# Test_Pack.net
KiCad netlist of a schematic drawn in EAGLE
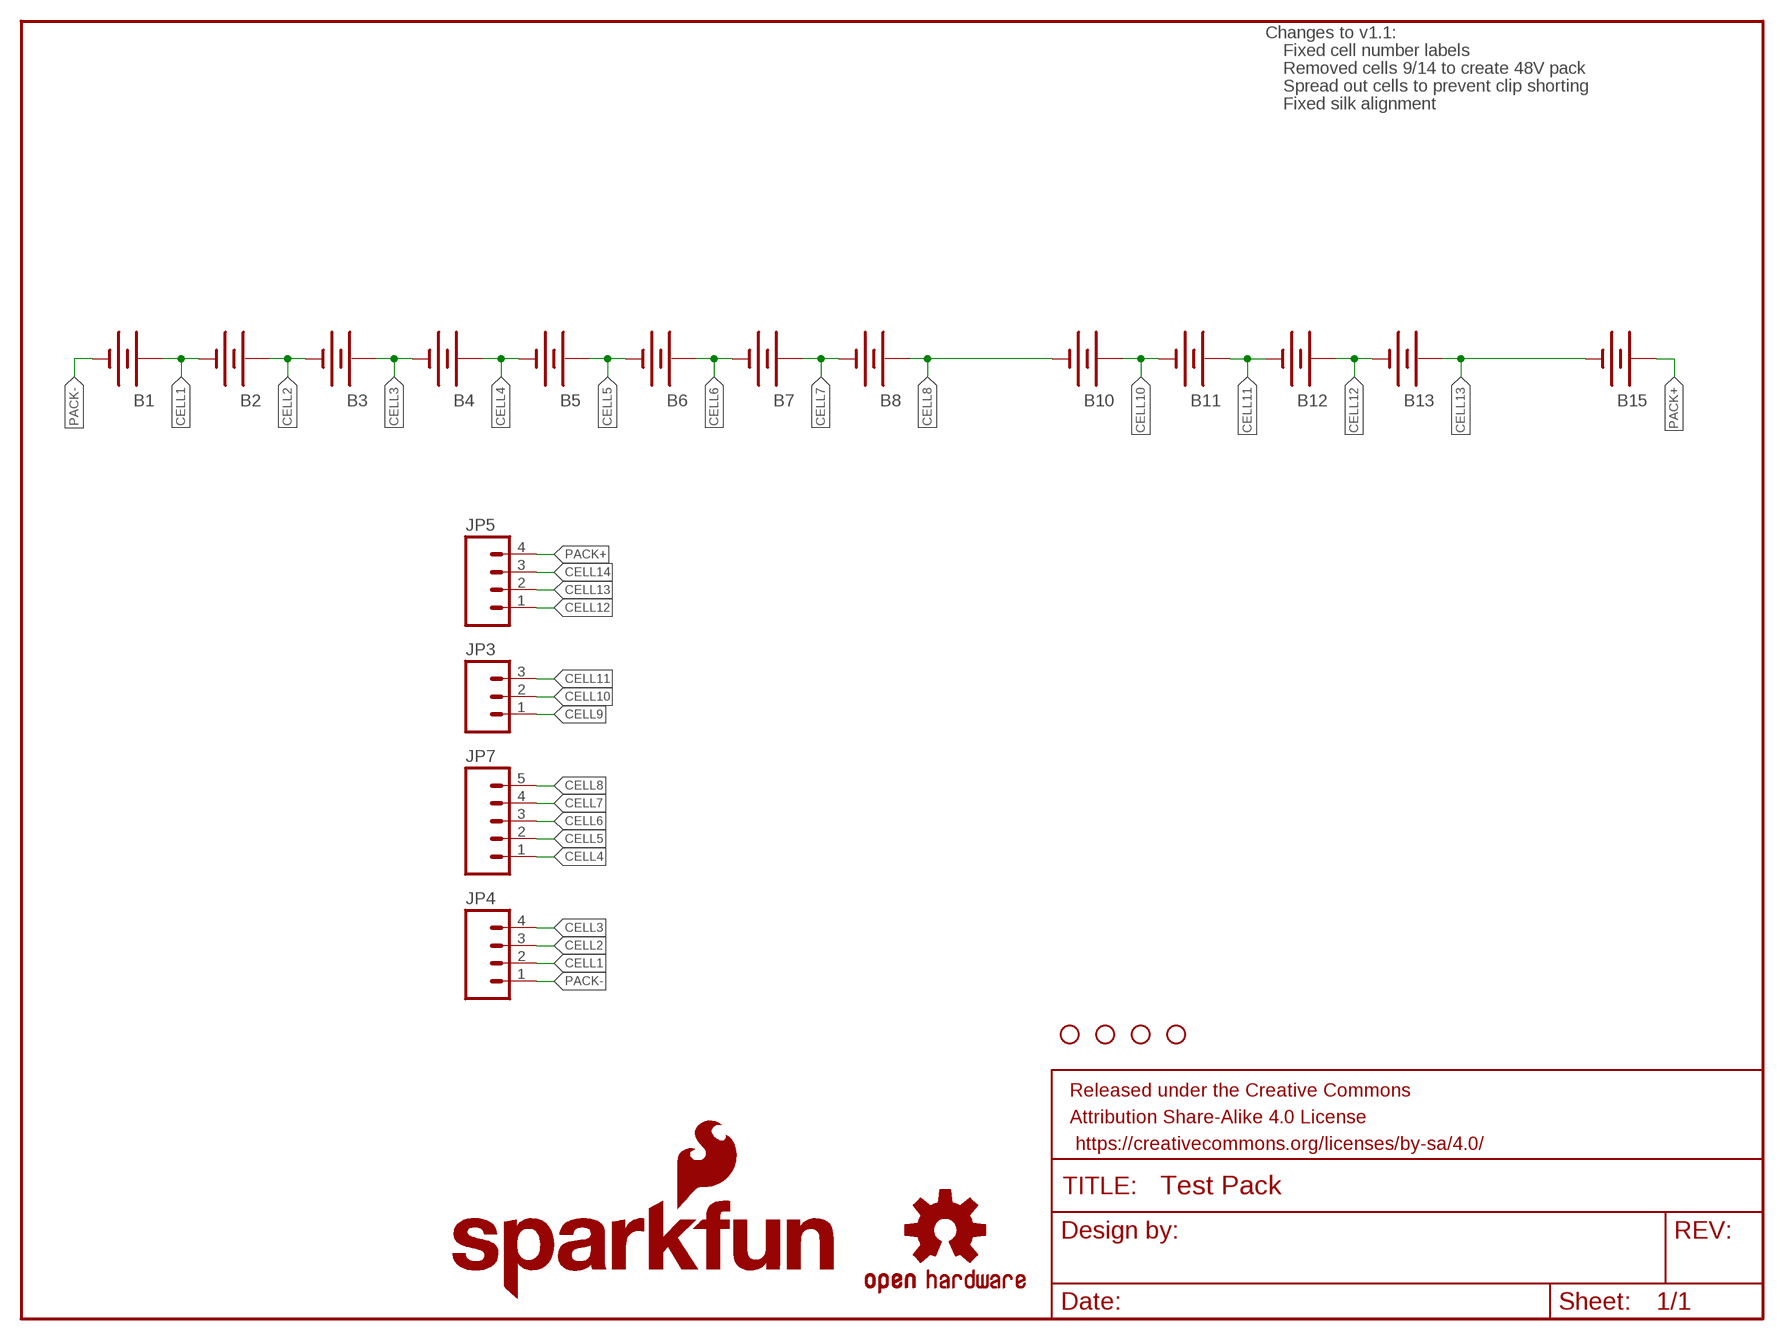
[diagram p0: schematic, sheet 1]

(export (version "E")
  (design (tool "Eeschema 10.0.6"))
  (components
    (comp (ref "B1")
      (value "BATTERY18650")
      (footprint "eagle-import:BATTERY_18650-HOLDER")
      (libsource (lib "eagle-import") (part "BATTERY18650"))
    )
    (comp (ref "B2")
      (value "BATTERY18650")
      (footprint "eagle-import:BATTERY_18650-HOLDER")
      (libsource (lib "eagle-import") (part "BATTERY18650"))
    )
    (comp (ref "B3")
      (value "BATTERY18650")
      (footprint "eagle-import:BATTERY_18650-HOLDER")
      (libsource (lib "eagle-import") (part "BATTERY18650"))
    )
    (comp (ref "B4")
      (value "BATTERY18650")
      (footprint "eagle-import:BATTERY_18650-HOLDER")
      (libsource (lib "eagle-import") (part "BATTERY18650"))
    )
    (comp (ref "B5")
      (value "BATTERY18650")
      (footprint "eagle-import:BATTERY_18650-HOLDER")
      (libsource (lib "eagle-import") (part "BATTERY18650"))
    )
    (comp (ref "B6")
      (value "BATTERY18650")
      (footprint "eagle-import:BATTERY_18650-HOLDER")
      (libsource (lib "eagle-import") (part "BATTERY18650"))
    )
    (comp (ref "B7")
      (value "BATTERY18650")
      (footprint "eagle-import:BATTERY_18650-HOLDER")
      (libsource (lib "eagle-import") (part "BATTERY18650"))
    )
    (comp (ref "B8")
      (value "BATTERY18650")
      (footprint "eagle-import:BATTERY_18650-HOLDER")
      (libsource (lib "eagle-import") (part "BATTERY18650"))
    )
    (comp (ref "B10")
      (value "BATTERY18650")
      (footprint "eagle-import:BATTERY_18650-HOLDER")
      (libsource (lib "eagle-import") (part "BATTERY18650"))
    )
    (comp (ref "B11")
      (value "BATTERY18650")
      (footprint "eagle-import:BATTERY_18650-HOLDER")
      (libsource (lib "eagle-import") (part "BATTERY18650"))
    )
    (comp (ref "B12")
      (value "BATTERY18650")
      (footprint "eagle-import:BATTERY_18650-HOLDER")
      (libsource (lib "eagle-import") (part "BATTERY18650"))
    )
    (comp (ref "B13")
      (value "BATTERY18650")
      (footprint "eagle-import:BATTERY_18650-HOLDER")
      (libsource (lib "eagle-import") (part "BATTERY18650"))
    )
    (comp (ref "B15")
      (value "BATTERY18650")
      (footprint "eagle-import:BATTERY_18650-HOLDER")
      (libsource (lib "eagle-import") (part "BATTERY18650"))
    )
    (comp (ref "FRAME1")
      (value "FRAME-LETTER")
      (footprint "eagle-import:CREATIVE_COMMONS")
      (libsource (lib "eagle-import") (part "FRAME-LETTER"))
    )
    (comp (ref "JP3")
      (value "M03JST-PTH")
      (footprint "eagle-import:JST-3-PTH")
      (libsource (lib "eagle-import") (part "M03JST-PTH"))
    )
    (comp (ref "JP4")
      (value "M04JST-PTH")
      (footprint "eagle-import:JST-4-PTH")
      (libsource (lib "eagle-import") (part "M04JST-PTH"))
    )
    (comp (ref "JP5")
      (value "M04JST-PTH")
      (footprint "eagle-import:JST-4-PTH")
      (libsource (lib "eagle-import") (part "M04JST-PTH"))
    )
    (comp (ref "JP7")
      (value "M05JST")
      (footprint "eagle-import:JST-5-PTH")
      (libsource (lib "eagle-import") (part "M05JST"))
    )
    (comp (ref "LOGO1")
      (value "SFE_LOGO_NAME_FLAME.1_INCH")
      (footprint "eagle-import:SFE_LOGO_NAME_FLAME_.1")
      (libsource (lib "eagle-import") (part "SFE_LOGO_NAME_FLAME.1_INCH"))
    )
    (comp (ref "STANDOFF1")
      (value "STAND-OFF")
      (footprint "eagle-import:STAND-OFF")
      (libsource (lib "eagle-import") (part "STAND-OFF"))
    )
    (comp (ref "STANDOFF2")
      (value "STAND-OFF")
      (footprint "eagle-import:STAND-OFF")
      (libsource (lib "eagle-import") (part "STAND-OFF"))
    )
    (comp (ref "STANDOFF3")
      (value "STAND-OFF")
      (footprint "eagle-import:STAND-OFF")
      (libsource (lib "eagle-import") (part "STAND-OFF"))
    )
    (comp (ref "STANDOFF4")
      (value "STAND-OFF")
      (footprint "eagle-import:STAND-OFF")
      (libsource (lib "eagle-import") (part "STAND-OFF"))
    )
    (comp (ref "U$7")
      (value "OSHW-LOGOS")
      (footprint "eagle-import:OSHW-LOGO-S")
      (libsource (lib "eagle-import") (part "OSHW-LOGOS"))
    )
  )
  (nets
    (net (code "1") (name "CELL1") (class "Default")
      (node (ref "B1") (pin "PWR@1") (pinfunction "+_PWR@1") (pintype "power_in"))
      (node (ref "B2") (pin "GND@1") (pinfunction "-_GND@1") (pintype "power_in"))
      (node (ref "JP4") (pin "2") (pinfunction "2_2") (pintype "passive"))
    )
    (net (code "2") (name "CELL2") (class "Default")
      (node (ref "B2") (pin "PWR@1") (pinfunction "+_PWR@1") (pintype "power_in"))
      (node (ref "B3") (pin "GND@1") (pinfunction "-_GND@1") (pintype "power_in"))
      (node (ref "JP4") (pin "3") (pinfunction "3_3") (pintype "passive"))
    )
    (net (code "3") (name "CELL3") (class "Default")
      (node (ref "B3") (pin "PWR@1") (pinfunction "+_PWR@1") (pintype "power_in"))
      (node (ref "B4") (pin "GND@1") (pinfunction "-_GND@1") (pintype "power_in"))
      (node (ref "JP4") (pin "4") (pinfunction "4_4") (pintype "passive"))
    )
    (net (code "4") (name "CELL4") (class "Default")
      (node (ref "B4") (pin "PWR@1") (pinfunction "+_PWR@1") (pintype "power_in"))
      (node (ref "B5") (pin "GND@1") (pinfunction "-_GND@1") (pintype "power_in"))
      (node (ref "JP7") (pin "1") (pinfunction "1_1") (pintype "passive"))
    )
    (net (code "5") (name "CELL5") (class "Default")
      (node (ref "B5") (pin "PWR@1") (pinfunction "+_PWR@1") (pintype "power_in"))
      (node (ref "B6") (pin "GND@1") (pinfunction "-_GND@1") (pintype "power_in"))
      (node (ref "JP7") (pin "2") (pinfunction "2_2") (pintype "passive"))
    )
    (net (code "6") (name "CELL6") (class "Default")
      (node (ref "B6") (pin "PWR@1") (pinfunction "+_PWR@1") (pintype "power_in"))
      (node (ref "B7") (pin "GND@1") (pinfunction "-_GND@1") (pintype "power_in"))
      (node (ref "JP7") (pin "3") (pinfunction "3_3") (pintype "passive"))
    )
    (net (code "7") (name "CELL7") (class "Default")
      (node (ref "B7") (pin "PWR@1") (pinfunction "+_PWR@1") (pintype "power_in"))
      (node (ref "B8") (pin "GND@1") (pinfunction "-_GND@1") (pintype "power_in"))
      (node (ref "JP7") (pin "4") (pinfunction "4_4") (pintype "passive"))
    )
    (net (code "8") (name "CELL8") (class "Default")
      (node (ref "B10") (pin "GND@1") (pinfunction "-_GND@1") (pintype "power_in"))
      (node (ref "B8") (pin "PWR@1") (pinfunction "+_PWR@1") (pintype "power_in"))
      (node (ref "JP7") (pin "5") (pinfunction "5_5") (pintype "passive"))
    )
    (net (code "9") (name "CELL9") (class "Default")
      (node (ref "JP3") (pin "1") (pinfunction "1_1") (pintype "passive"))
    )
    (net (code "10") (name "CELL10") (class "Default")
      (node (ref "B10") (pin "PWR@1") (pinfunction "+_PWR@1") (pintype "power_in"))
      (node (ref "B11") (pin "GND@1") (pinfunction "-_GND@1") (pintype "power_in"))
      (node (ref "JP3") (pin "2") (pinfunction "2_2") (pintype "passive"))
    )
    (net (code "11") (name "CELL11") (class "Default")
      (node (ref "B11") (pin "PWR@1") (pinfunction "+_PWR@1") (pintype "power_in"))
      (node (ref "B12") (pin "GND@1") (pinfunction "-_GND@1") (pintype "power_in"))
      (node (ref "JP3") (pin "3") (pinfunction "3_3") (pintype "passive"))
    )
    (net (code "12") (name "CELL12") (class "Default")
      (node (ref "B12") (pin "PWR@1") (pinfunction "+_PWR@1") (pintype "power_in"))
      (node (ref "B13") (pin "GND@1") (pinfunction "-_GND@1") (pintype "power_in"))
      (node (ref "JP5") (pin "1") (pinfunction "1_1") (pintype "passive"))
    )
    (net (code "13") (name "CELL13") (class "Default")
      (node (ref "B13") (pin "PWR@1") (pinfunction "+_PWR@1") (pintype "power_in"))
      (node (ref "B15") (pin "GND@1") (pinfunction "-_GND@1") (pintype "power_in"))
      (node (ref "JP5") (pin "2") (pinfunction "2_2") (pintype "passive"))
    )
    (net (code "14") (name "CELL14") (class "Default")
      (node (ref "JP5") (pin "3") (pinfunction "3_3") (pintype "passive"))
    )
    (net (code "15") (name "PACK+") (class "Default")
      (node (ref "B15") (pin "PWR@1") (pinfunction "+_PWR@1") (pintype "power_in"))
      (node (ref "JP5") (pin "4") (pinfunction "4_4") (pintype "passive"))
    )
    (net (code "16") (name "PACK-") (class "Default")
      (node (ref "B1") (pin "GND@1") (pinfunction "-_GND@1") (pintype "power_in"))
      (node (ref "JP4") (pin "1") (pinfunction "1_1") (pintype "passive"))
    )
  )
)
